# ideal-diode.net
KiCad netlist of a schematic drawn in Altium Designer
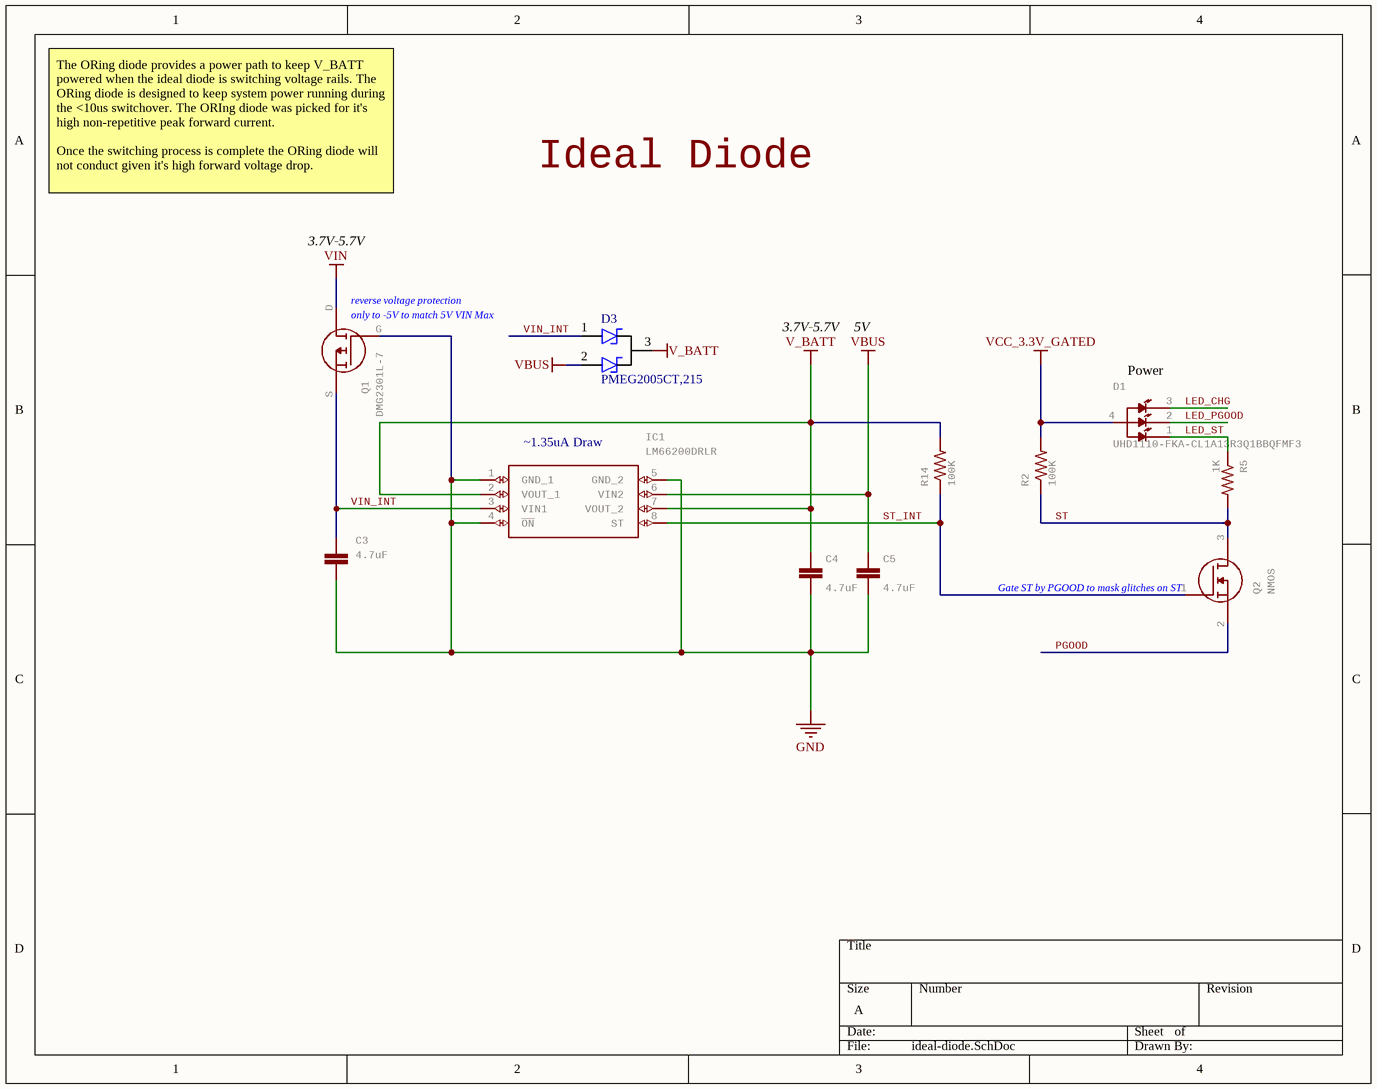
[diagram p0: ideal-diode.SchDoc]

(export (version "E")
  (design (tool "Eeschema 10.0.6"))
  (components
    (comp (ref "C3")
      (value "4.7uF")
      (footprint "0402-CAP")
      (description "CapacitorStandard 0603 ceramic capacitor, and 0.1\" leaded capacitor.")
      (fields (field (name "MPN") "JMK105BBJ475MV-F"))
      (libsource (lib "rt10") (part "CAP0402-CAP"))
    )
    (comp (ref "C4")
      (value "4.7uF")
      (footprint "0402-CAP")
      (description "CapacitorStandard 0603 ceramic capacitor, and 0.1\" leaded capacitor.")
      (fields (field (name "MPN") "JMK105BBJ475MV-F"))
      (libsource (lib "rt10") (part "CAP0402-CAP"))
    )
    (comp (ref "C5")
      (value "4.7uF")
      (footprint "0402-CAP")
      (description "CapacitorStandard 0603 ceramic capacitor, and 0.1\" leaded capacitor.")
      (fields (field (name "MPN") "JMK105BBJ475MV-F"))
      (libsource (lib "rt10") (part "CAP0402-CAP"))
    )
    (comp (ref "D1")
      (value "UHD1110-FKA-CL1A13R3Q1BBQFMF3")
      (footprint "LED_UHD1110-FKA-CL1A13R3Q1BBQFMF3")
      (description "LED RGB SMD, SIZE 1 X 1 mm Check availability")
      (fields (field (name "MF") "Cree Inc.") (field (name "MPN") "UHD1110-FKA-CL1A13r3q1BBQFMF3"))
      (libsource (lib "rt10") (part "UHD1110-FKA-CL1A13R3Q1BBQFMF3"))
    )
    (comp (ref "D3")
      (value "Dual Schottky")
      (footprint "SOT-23-3")
      (fields
        (field (name "MANUFACTURER") "Nexperia")
        (field (name "PART NUMBER") "PMEG2005CT,215")
        (field (name "MPN") "PMEG2005CT,215")
      )
      (libsource (lib "openmv-ae3") (part "Dual Schottky"))
    )
    (comp (ref "IC1")
      (value "LM66200DRLR")
      (footprint "SOTFL50P160X60-8N")
      (description "1.6-V to 5.5-V, 40-m, 2.5-A, low-IQ, dual ideal diode   Source:  Datasheet")
      (fields (field (name "MOUSER_PART_NUMBER") "595-LM66200DRLR"))
      (libsource (lib "rt10") (part "LM66200DRLR"))
    )
    (comp (ref "Q1")
      (value "DMG2301L-7")
      (footprint "SOT-23-3-FET")
      (libsource (lib "openmv-ae3") (part "DMG2301L-7"))
    )
    (comp (ref "Q2")
      (value "NMOS")
      (footprint "DFN1006")
      (description "MOSFET 60V N-Channel Enhancement Mode MOSFET - ESD Protected   Source:  Datasheet")
      (libsource (lib "rt10") (part "2N7002KW_R1_00001"))
    )
    (comp (ref "R2")
      (value "100K")
      (footprint "0402-RES")
      (description "ResistorBasic schematic elements and footprints for 0603, 1206, and PTH resistors.")
      (fields (field (name "MPN") "AC0402FR-07100KL"))
      (libsource (lib "rt10") (part "RESISTOR0402-RES"))
    )
    (comp (ref "R5")
      (value "1K")
      (footprint "0402-RES")
      (description "ResistorBasic schematic elements and footprints for 0603, 1206, and PTH resistors.")
      (fields (field (name "MPN") "CRCW04021K00FKEDC"))
      (libsource (lib "rt10") (part "RESISTOR0402-RES"))
    )
    (comp (ref "R14")
      (value "100K")
      (footprint "0402-RES")
      (description "ResistorBasic schematic elements and footprints for 0603, 1206, and PTH resistors.")
      (fields (field (name "MPN") "AC0402FR-07100KL"))
      (libsource (lib "rt10") (part "RESISTOR0402-RES"))
    )
  )
  (nets
    (net (code "1") (name "/LED_CHG") (class "Default")
      (node (ref "D1") (pin "3") (pinfunction "RED_3") (pintype "passive"))
    )
    (net (code "2") (name "/LED_PGOOD") (class "Default")
      (node (ref "D1") (pin "2") (pinfunction "GREEN_2") (pintype "passive"))
    )
    (net (code "3") (name "/LED_ST") (class "Default")
      (node (ref "D1") (pin "1") (pinfunction "BLUE_1") (pintype "passive"))
      (node (ref "R5") (pin "1") (pinfunction "1_1") (pintype "passive"))
    )
    (net (code "4") (name "/PGOOD") (class "Default")
      (node (ref "Q2") (pin "2") (pinfunction "S_2") (pintype "bidirectional"))
    )
    (net (code "5") (name "/ST") (class "Default")
      (node (ref "Q2") (pin "3") (pinfunction "D_3") (pintype "bidirectional"))
      (node (ref "R2") (pin "1") (pinfunction "1_1") (pintype "passive"))
      (node (ref "R5") (pin "2") (pinfunction "2_2") (pintype "passive"))
    )
    (net (code "6") (name "/ST_INT") (class "Default")
      (node (ref "IC1") (pin "8") (pinfunction "ST_8") (pintype "bidirectional"))
      (node (ref "Q2") (pin "1") (pinfunction "G_1") (pintype "bidirectional"))
      (node (ref "R14") (pin "1") (pinfunction "1_1") (pintype "passive"))
    )
    (net (code "7") (name "/VIN_INT") (class "Default")
      (node (ref "C3") (pin "2") (pinfunction "2_2") (pintype "passive"))
      (node (ref "D3") (pin "1") (pinfunction "1_1") (pintype "passive"))
      (node (ref "IC1") (pin "3") (pinfunction "VIN1_3") (pintype "bidirectional"))
      (node (ref "Q1") (pin "S") (pinfunction "S_S") (pintype "bidirectional"))
    )
    (net (code "8") (name "GND") (class "Default")
      (node (ref "C3") (pin "1") (pinfunction "1_1") (pintype "passive"))
      (node (ref "C4") (pin "1") (pinfunction "1_1") (pintype "passive"))
      (node (ref "C5") (pin "1") (pinfunction "1_1") (pintype "passive"))
      (node (ref "IC1") (pin "1") (pinfunction "GND_1_1") (pintype "bidirectional"))
      (node (ref "IC1") (pin "4") (pinfunction "~{ON}_4") (pintype "bidirectional"))
      (node (ref "IC1") (pin "5") (pinfunction "GND_2_5") (pintype "bidirectional"))
      (node (ref "Q1") (pin "G") (pinfunction "G_G") (pintype "bidirectional"))
    )
    (net (code "9") (name "VBUS") (class "Default")
      (node (ref "C5") (pin "2") (pinfunction "2_2") (pintype "passive"))
      (node (ref "D3") (pin "2") (pinfunction "2_2") (pintype "passive"))
      (node (ref "IC1") (pin "6") (pinfunction "VIN2_6") (pintype "bidirectional"))
    )
    (net (code "10") (name "VCC_3.3V_GATED") (class "Default")
      (node (ref "D1") (pin "4") (pinfunction "ANODE_4") (pintype "passive"))
      (node (ref "R2") (pin "2") (pinfunction "2_2") (pintype "passive"))
    )
    (net (code "11") (name "VIN") (class "Default")
      (node (ref "Q1") (pin "D") (pinfunction "D_D") (pintype "bidirectional"))
    )
    (net (code "12") (name "V_BATT") (class "Default")
      (node (ref "C4") (pin "2") (pinfunction "2_2") (pintype "passive"))
      (node (ref "D3") (pin "3") (pinfunction "3_3") (pintype "passive"))
      (node (ref "IC1") (pin "2") (pinfunction "VOUT_1_2") (pintype "bidirectional"))
      (node (ref "IC1") (pin "7") (pinfunction "VOUT_2_7") (pintype "bidirectional"))
      (node (ref "R14") (pin "2") (pinfunction "2_2") (pintype "passive"))
    )
  )
)
